# Power.net
KiCad netlist of a schematic drawn in Altium Designer
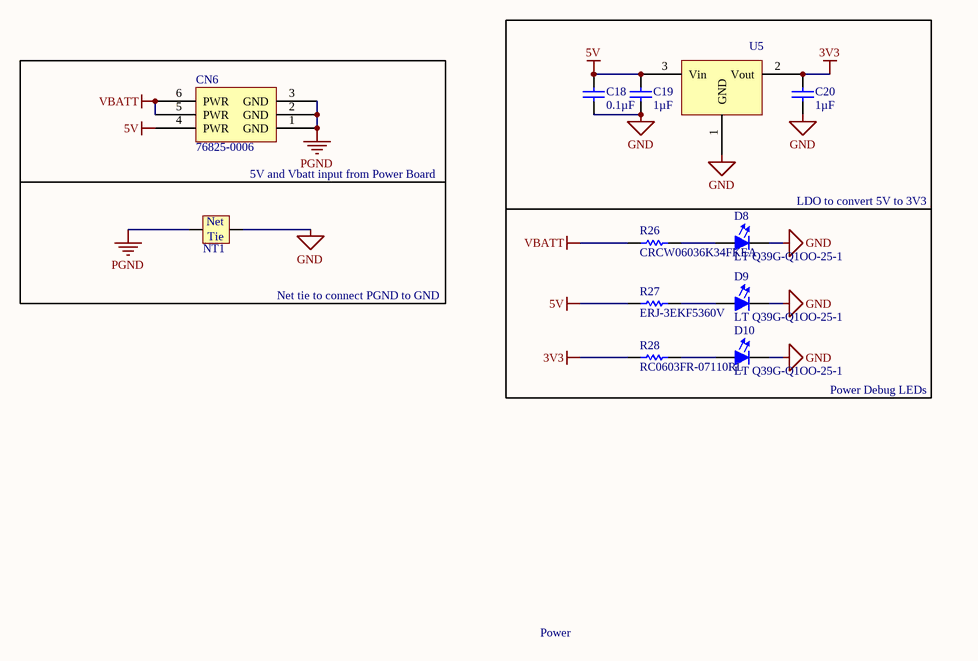
[diagram p0: Power.SchDoc]

(export (version "E")
  (design (tool "Eeschema 10.0.6"))
  (components
    (comp (ref "C18")
      (value "0.1uF, 50V, 10%, X7R, 1608")
      (footprint "CAPC1608N(0603\")")
      (description "CAP CER 0.1UF 50V 10% X7R 1608 (0603)")
      (fields
        (field (name "MANUFACTURER") "Samsung Electro-Mechanics America, Inc")
        (field (name "CAPACITANCE") "0.1µF")
        (field (name "TOLERANCE") "±10%")
      )
      (libsource (lib "AUVIC") (part "Symbol"))
    )
    (comp (ref "C19")
      (value "1µF")
      (footprint "CAPC1608N(0603\")")
      (description "Capacitor, Ceramic, 50V, +/- 10%, 0603 SMD, X5R")
      (fields (field (name "Comment") "1uF 50V 0603 SMD, Ceramic") (field (name "CREATED BY") "Lyden Smith"))
      (libsource (lib "AUVIC") (part "Symbol"))
    )
    (comp (ref "C20")
      (value "1µF")
      (footprint "CAPC1608N(0603\")")
      (description "Capacitor, Ceramic, 50V, +/- 10%, 0603 SMD, X5R")
      (fields (field (name "Comment") "1uF 50V 0603 SMD, Ceramic") (field (name "CREATED BY") "Lyden Smith"))
      (libsource (lib "AUVIC") (part "Symbol"))
    )
    (comp (ref "CN6")
      (value "76825-0006")
      (footprint "76825-0006-Footprint-1")
      (libsource (lib "AUVIC") (part "76825-0006"))
    )
    (comp (ref "D8")
      (value "LT Q39G-Q1OO-25-1")
      (footprint "FP-LB_Q39E-MFG")
      (description "LED GREEN DIFFUSED 0603 SMD")
      (libsource (lib "") (part "Symbol_1"))
    )
    (comp (ref "D9")
      (value "LT Q39G-Q1OO-25-1")
      (footprint "FP-LB_Q39E-MFG")
      (description "LED GREEN DIFFUSED 0603 SMD")
      (libsource (lib "") (part "Symbol_1"))
    )
    (comp (ref "D10")
      (value "LT Q39G-Q1OO-25-1")
      (footprint "FP-LB_Q39E-MFG")
      (description "LED GREEN DIFFUSED 0603 SMD")
      (libsource (lib "") (part "Symbol_1"))
    )
    (comp (ref "NT1")
      (value "Net Tie, 20mil")
      (footprint "NETTIE_20mil")
      (description "Net Tie, 20mil by 20mil")
      (fields
        (field (name "PUBLISHER") "AUVic")
        (field (name "SOURCE") "AUVic_Integrated_Library_Virtual_Components.SchLib")
        (field (name "CREATED BY") "Ashwin Sira")
      )
      (libsource (lib "") (part "Symbol_2"))
    )
    (comp (ref "R26")
      (value "CRCW06036K34FKEA")
      (footprint "RESC1609X50X30ML10T20")
      (fields (field (name "TOLERANCE") "1%"))
      (libsource (lib "AUVIC") (part "RES"))
    )
    (comp (ref "R27")
      (value "ERJ-3EKF5360V")
      (footprint "RESC1608X55X30ML15T15")
      (description "SMD Chip Resistor, 0603 [1608 Metric], 536 ohm, ERJ3EK Series, 75 V, Thick Film, 100 mW")
      (fields (field (name "TOLERANCE") "1%"))
      (libsource (lib "AUVIC") (part "RES"))
    )
    (comp (ref "R28")
      (value "RC0603FR-07110RL")
      (footprint "RESC1608X55X25ML10T15")
      (description "RES SMD 110 OHM 1% 1/10W 0603")
      (fields (field (name "TOLERANCE") "1%"))
      (libsource (lib "AUVIC") (part "RES"))
    )
    (comp (ref "U5")
      (value "3.3V 250mA Linear Reg LDO")
      (footprint "SOT95P245X110-3N")
      (description "IC REG LINEAR 3.3V 250MA SOT23-3")
      (fields (field (name "CREATED BY") "Poorna Chander Kalidas"))
      (libsource (lib "AUVIC") (part "3.3V 250mA Linear Reg LDO"))
    )
  )
  (nets
    (net (code "1") (name "3V3") (class "Default")
      (node (ref "C20") (pin "2") (pinfunction "Cathode_2") (pintype "passive"))
      (node (ref "R28") (pin "1") (pinfunction "1_1") (pintype "passive"))
      (node (ref "U5") (pin "2") (pinfunction "Vout_2") (pintype "power_in"))
    )
    (net (code "2") (name "5V") (class "Default")
      (node (ref "C18") (pin "2") (pinfunction "Cathode_2") (pintype "passive"))
      (node (ref "C19") (pin "2") (pinfunction "Cathode_2") (pintype "passive"))
      (node (ref "CN6") (pin "4") (pinfunction "PWR_4") (pintype "passive"))
      (node (ref "R27") (pin "1") (pinfunction "1_1") (pintype "passive"))
      (node (ref "U5") (pin "3") (pinfunction "Vin_3") (pintype "power_in"))
    )
    (net (code "3") (name "GND") (class "Default")
      (node (ref "C18") (pin "1") (pinfunction "Anode_1") (pintype "passive"))
      (node (ref "C19") (pin "1") (pinfunction "Anode_1") (pintype "passive"))
      (node (ref "C20") (pin "1") (pinfunction "Anode_1") (pintype "passive"))
      (node (ref "D10") (pin "1") (pinfunction "Cathode_1") (pintype "passive"))
      (node (ref "D8") (pin "1") (pinfunction "Cathode_1") (pintype "passive"))
      (node (ref "D9") (pin "1") (pinfunction "Cathode_1") (pintype "passive"))
      (node (ref "NT1") (pin "2") (pinfunction "2_2") (pintype "passive"))
      (node (ref "U5") (pin "1") (pinfunction "GND_1") (pintype "power_in"))
    )
    (net (code "4") (name "Net-(D8-Anode)") (class "Default")
      (node (ref "D8") (pin "2") (pinfunction "Anode_2") (pintype "passive"))
      (node (ref "R26") (pin "2") (pinfunction "2_2") (pintype "passive"))
    )
    (net (code "5") (name "Net-(D9-Anode)") (class "Default")
      (node (ref "D9") (pin "2") (pinfunction "Anode_2") (pintype "passive"))
      (node (ref "R27") (pin "2") (pinfunction "2_2") (pintype "passive"))
    )
    (net (code "6") (name "Net-(D10-Anode)") (class "Default")
      (node (ref "D10") (pin "2") (pinfunction "Anode_2") (pintype "passive"))
      (node (ref "R28") (pin "2") (pinfunction "2_2") (pintype "passive"))
    )
    (net (code "7") (name "PGND") (class "Default")
      (node (ref "CN6") (pin "1") (pinfunction "GND_1") (pintype "passive"))
      (node (ref "CN6") (pin "2") (pinfunction "GND_2") (pintype "passive"))
      (node (ref "CN6") (pin "3") (pinfunction "GND_3") (pintype "passive"))
      (node (ref "NT1") (pin "1") (pinfunction "1_1") (pintype "passive"))
    )
    (net (code "8") (name "VBATT") (class "Default")
      (node (ref "CN6") (pin "5") (pinfunction "PWR_5") (pintype "passive"))
      (node (ref "CN6") (pin "6") (pinfunction "PWR_6") (pintype "passive"))
      (node (ref "R26") (pin "1") (pinfunction "1_1") (pintype "passive"))
    )
  )
)
